# zamek.net
KiCad netlist of a schematic drawn in EAGLE
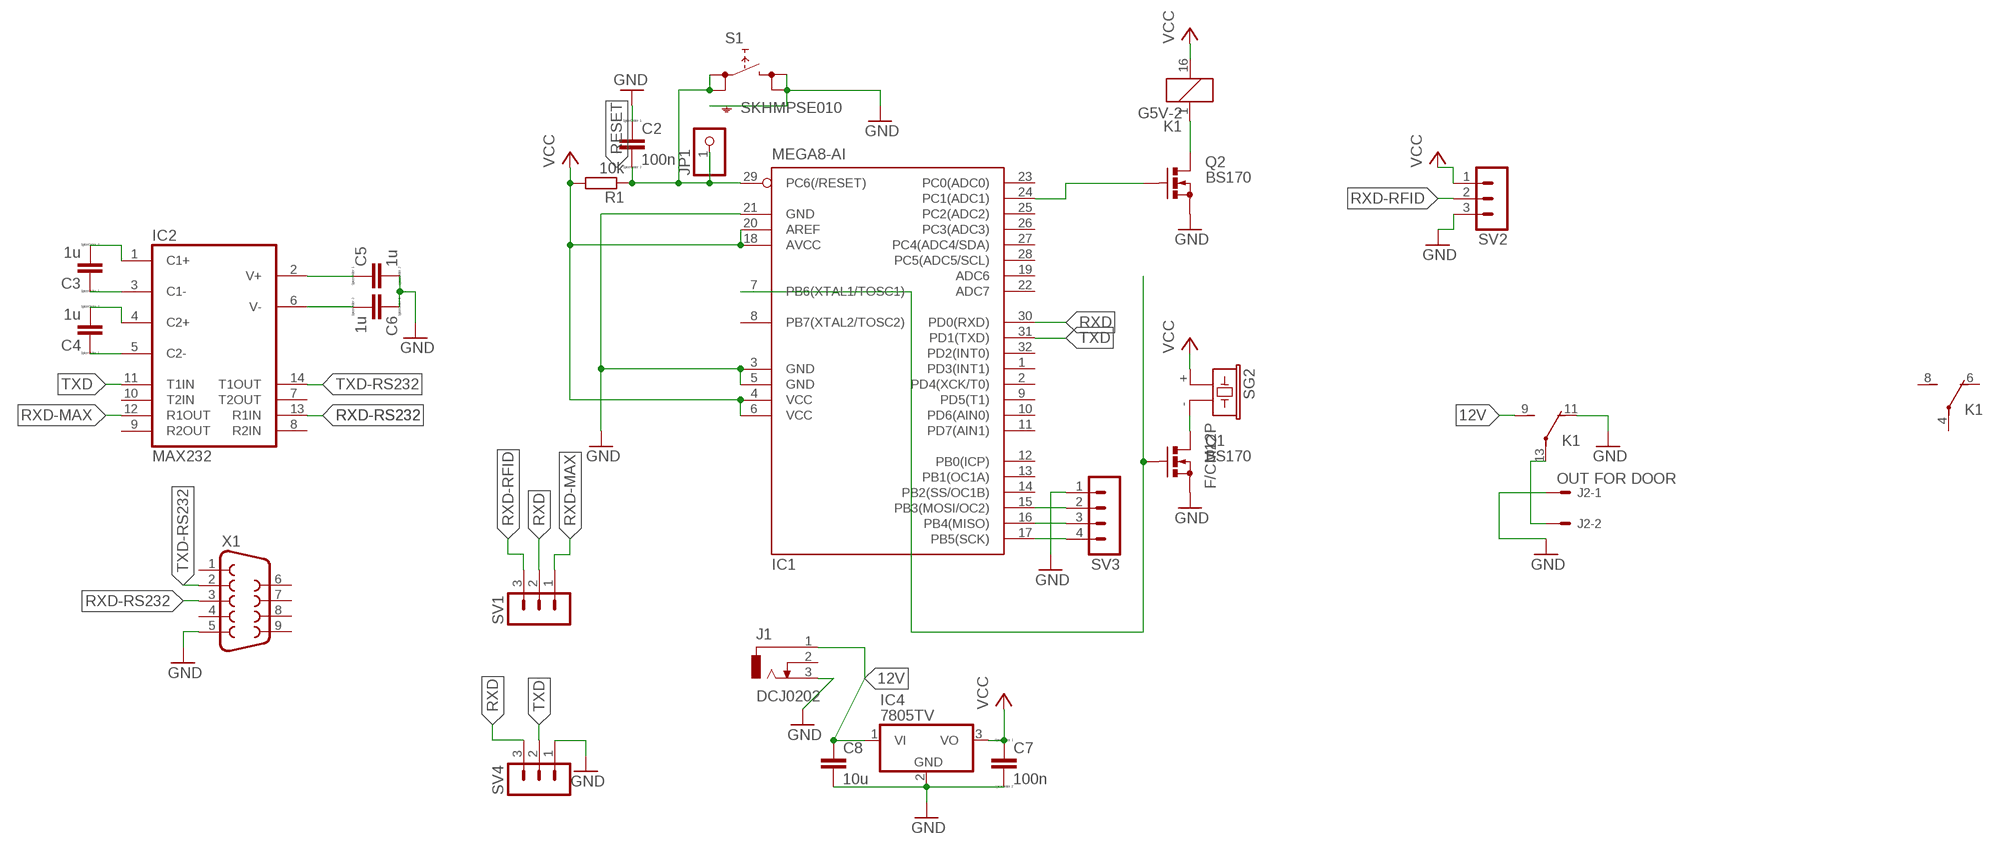
[diagram p0: schematic, sheet 1]

(export (version "E")
  (design (tool "Eeschema 10.0.6"))
  (components
    (comp (ref "C2")
      (value "100n")
      (footprint "eagle-import:C1206")
      (libsource (lib "eagle-import") (part "CC1206"))
    )
    (comp (ref "C3")
      (value "1u")
      (footprint "eagle-import:C1206")
      (libsource (lib "eagle-import") (part "CC1206"))
    )
    (comp (ref "C4")
      (value "1u")
      (footprint "eagle-import:C1206")
      (libsource (lib "eagle-import") (part "CC1206"))
    )
    (comp (ref "C5")
      (value "1u")
      (footprint "eagle-import:C1206")
      (libsource (lib "eagle-import") (part "CC1206"))
    )
    (comp (ref "C6")
      (value "1u")
      (footprint "eagle-import:C1206")
      (libsource (lib "eagle-import") (part "CC1206"))
    )
    (comp (ref "C7")
      (value "100n")
      (footprint "eagle-import:C1206")
      (libsource (lib "eagle-import") (part "CC1206"))
    )
    (comp (ref "C8")
      (value "10u")
      (footprint "eagle-import:C5B3")
      (libsource (lib "eagle-import") (part "C5/3"))
    )
    (comp (ref "IC1")
      (value "MEGA8-AI")
      (footprint "eagle-import:TQFP32-08")
      (fields (field (name "MPN") "ATMEGA8-16AU"))
      (libsource (lib "eagle-import") (part "MEGA8-AI"))
    )
    (comp (ref "IC2")
      (value "MAX232")
      (footprint "eagle-import:DIL16")
      (fields (field (name "MF") "MAXIM") (field (name "MPN") "MAX232ACPE+"))
      (libsource (lib "eagle-import") (part "MAX232"))
    )
    (comp (ref "IC4")
      (value "7805TV")
      (footprint "eagle-import:TO220V")
      (libsource (lib "eagle-import") (part "78TV05"))
    )
    (comp (ref "J1")
      (value "DCJ0202")
      (footprint "eagle-import:DCJ0202")
      (libsource (lib "eagle-import") (part "DCJ0202"))
    )
    (comp (ref "J2")
      (value "OUT FOR DOOR")
      (footprint "eagle-import:6410-02")
      (libsource (lib "eagle-import") (part "22-?-0227-2021"))
    )
    (comp (ref "JP1")
      (value "PINHD-1X1")
      (footprint "eagle-import:1X01")
      (libsource (lib "eagle-import") (part "PINHD-1X1"))
    )
    (comp (ref "K1")
      (value "G5V-2")
      (footprint "eagle-import:G5V-2")
      (fields (field (name "MPN") "G5V-2 5DC"))
      (libsource (lib "eagle-import") (part "G5V-2"))
    )
    (comp (ref "Q1")
      (value "BS170")
      (footprint "eagle-import:SOT54E")
      (libsource (lib "eagle-import") (part "BS170"))
    )
    (comp (ref "Q2")
      (value "BS170")
      (footprint "eagle-import:SOT54E")
      (libsource (lib "eagle-import") (part "BS170"))
    )
    (comp (ref "R1")
      (value "10k")
      (footprint "eagle-import:R1206")
      (libsource (lib "eagle-import") (part "R-EU_R1206"))
    )
    (comp (ref "S1")
      (value "SKHMPSE010")
      (footprint "eagle-import:SKHMPXE010")
      (libsource (lib "eagle-import") (part "SKHMPE010S"))
    )
    (comp (ref "SG2")
      (value "F/CM12P")
      (footprint "eagle-import:F_CM12P")
      (libsource (lib "eagle-import") (part "F/CM12P"))
    )
    (comp (ref "SV1")
      (value "MA03-1")
      (footprint "eagle-import:MA03-1")
      (libsource (lib "eagle-import") (part "MA03-1"))
    )
    (comp (ref "SV2")
      (value "MA03-1")
      (footprint "eagle-import:MA03-1")
      (libsource (lib "eagle-import") (part "MA03-1"))
    )
    (comp (ref "SV3")
      (value "MA04-1")
      (footprint "eagle-import:MA04-1")
      (libsource (lib "eagle-import") (part "MA04-1"))
    )
    (comp (ref "SV4")
      (value "MA03-1")
      (footprint "eagle-import:MA03-1")
      (libsource (lib "eagle-import") (part "MA03-1"))
    )
    (comp (ref "X1")
      (value "F09HP")
      (footprint "eagle-import:F09HP")
      (libsource (lib "eagle-import") (part "F09HP"))
    )
  )
  (nets
    (net (code "1") (name "12V") (class "Default")
      (node (ref "C8") (pin "1") (pinfunction "1_1") (pintype "passive"))
      (node (ref "IC4") (pin "1") (pinfunction "VI_1") (pintype "input"))
      (node (ref "J1") (pin "1") (pinfunction "1_1") (pintype "passive"))
      (node (ref "K1") (pin "9") (pinfunction "S_9") (pintype "passive"))
    )
    (net (code "2") (name "GND") (class "Default")
      (node (ref "C2") (pin "1") (pinfunction "1_1") (pintype "passive"))
      (node (ref "C5") (pin "2") (pinfunction "2_2") (pintype "passive"))
      (node (ref "C6") (pin "1") (pinfunction "1_1") (pintype "passive"))
      (node (ref "C7") (pin "2") (pinfunction "2_2") (pintype "passive"))
      (node (ref "C8") (pin "2") (pinfunction "2_2") (pintype "passive"))
      (node (ref "IC1") (pin "21") (pinfunction "GND_21") (pintype "power_in"))
      (node (ref "IC1") (pin "3") (pinfunction "GND_3") (pintype "power_in"))
      (node (ref "IC1") (pin "5") (pinfunction "GND_5") (pintype "power_in"))
      (node (ref "IC4") (pin "2") (pinfunction "GND_2") (pintype "passive"))
      (node (ref "J1") (pin "3") (pinfunction "3_3") (pintype "passive"))
      (node (ref "J2") (pin "1") (pinfunction "S_1") (pintype "passive"))
      (node (ref "K1") (pin "11") (pinfunction "O_11") (pintype "passive"))
      (node (ref "Q1") (pin "S") (pinfunction "S_S") (pintype "passive"))
      (node (ref "Q2") (pin "S") (pinfunction "S_S") (pintype "passive"))
      (node (ref "S1") (pin "3") (pinfunction "2.1_3") (pintype "passive"))
      (node (ref "S1") (pin "4") (pinfunction "2.2_4") (pintype "passive"))
      (node (ref "S1") (pin "5") (pinfunction "SH_5") (pintype "passive"))
      (node (ref "SV2") (pin "3") (pinfunction "3_3") (pintype "passive"))
      (node (ref "SV3") (pin "1") (pinfunction "1_1") (pintype "passive"))
      (node (ref "SV4") (pin "1") (pinfunction "1_1") (pintype "passive"))
      (node (ref "X1") (pin "5") (pinfunction "5_5") (pintype "passive"))
    )
    (net (code "3") (name "Net-(IC1-PB3(MOSI{slash}OC2))") (class "Default")
      (node (ref "IC1") (pin "15") (pinfunction "PB3(MOSI/OC2)_15") (pintype "bidirectional"))
      (node (ref "SV3") (pin "2") (pinfunction "2_2") (pintype "passive"))
    )
    (net (code "4") (name "Net-(IC1-PB4(MISO))") (class "Default")
      (node (ref "IC1") (pin "16") (pinfunction "PB4(MISO)_16") (pintype "bidirectional"))
      (node (ref "SV3") (pin "3") (pinfunction "3_3") (pintype "passive"))
    )
    (net (code "5") (name "Net-(IC1-PB5(SCK))") (class "Default")
      (node (ref "IC1") (pin "17") (pinfunction "PB5(SCK)_17") (pintype "bidirectional"))
      (node (ref "SV3") (pin "4") (pinfunction "4_4") (pintype "passive"))
    )
    (net (code "6") (name "Net-(IC1-PB6(XTAL1{slash}TOSC1))") (class "Default")
      (node (ref "IC1") (pin "7") (pinfunction "PB6(XTAL1/TOSC1)_7") (pintype "bidirectional"))
      (node (ref "Q1") (pin "G") (pinfunction "G_G") (pintype "passive"))
    )
    (net (code "7") (name "Net-(IC1-PC1(ADC1))") (class "Default")
      (node (ref "IC1") (pin "24") (pinfunction "PC1(ADC1)_24") (pintype "bidirectional"))
      (node (ref "Q2") (pin "G") (pinfunction "G_G") (pintype "passive"))
    )
    (net (code "8") (name "Net-(IC2A-C1+)") (class "Default")
      (node (ref "C3") (pin "2") (pinfunction "2_2") (pintype "passive"))
      (node (ref "IC2") (pin "1") (pinfunction "C1+_1") (pintype "bidirectional"))
    )
    (net (code "9") (name "Net-(IC2A-C1-)") (class "Default")
      (node (ref "C3") (pin "1") (pinfunction "1_1") (pintype "passive"))
      (node (ref "IC2") (pin "3") (pinfunction "C1-_3") (pintype "bidirectional"))
    )
    (net (code "10") (name "Net-(IC2A-C2+)") (class "Default")
      (node (ref "C4") (pin "2") (pinfunction "2_2") (pintype "passive"))
      (node (ref "IC2") (pin "4") (pinfunction "C2+_4") (pintype "bidirectional"))
    )
    (net (code "11") (name "Net-(IC2A-C2-)") (class "Default")
      (node (ref "C4") (pin "1") (pinfunction "1_1") (pintype "passive"))
      (node (ref "IC2") (pin "5") (pinfunction "C2-_5") (pintype "bidirectional"))
    )
    (net (code "12") (name "Net-(IC2A-V+)") (class "Default")
      (node (ref "C5") (pin "1") (pinfunction "1_1") (pintype "passive"))
      (node (ref "IC2") (pin "2") (pinfunction "V+_2") (pintype "bidirectional"))
    )
    (net (code "13") (name "Net-(IC2A-V-)") (class "Default")
      (node (ref "C6") (pin "2") (pinfunction "2_2") (pintype "passive"))
      (node (ref "IC2") (pin "6") (pinfunction "V-_6") (pintype "bidirectional"))
    )
    (net (code "14") (name "Net-(J2B-S)") (class "Default")
      (node (ref "J2") (pin "2") (pinfunction "S_2") (pintype "passive"))
      (node (ref "K1") (pin "13") (pinfunction "P_13") (pintype "passive"))
    )
    (net (code "15") (name "Net-(K1-Pad1)") (class "Default")
      (node (ref "K1") (pin "1") (pinfunction "1_1") (pintype "passive"))
      (node (ref "Q2") (pin "D") (pinfunction "D_D") (pintype "passive"))
    )
    (net (code "16") (name "Net-(SG2-2)") (class "Default")
      (node (ref "Q1") (pin "D") (pinfunction "D_D") (pintype "passive"))
      (node (ref "SG2") (pin "-") (pinfunction "2_-") (pintype "passive"))
    )
    (net (code "17") (name "RESET") (class "Default")
      (node (ref "C2") (pin "2") (pinfunction "2_2") (pintype "passive"))
      (node (ref "IC1") (pin "29") (pinfunction "PC6(/RESET)_29") (pintype "bidirectional"))
      (node (ref "JP1") (pin "1") (pinfunction "1_1") (pintype "passive"))
      (node (ref "R1") (pin "1") (pinfunction "1_1") (pintype "passive"))
      (node (ref "S1") (pin "1") (pinfunction "1.1_1") (pintype "passive"))
      (node (ref "S1") (pin "2") (pinfunction "1.2_2") (pintype "passive"))
    )
    (net (code "18") (name "RXD") (class "Default")
      (node (ref "IC1") (pin "30") (pinfunction "PD0(RXD)_30") (pintype "bidirectional"))
      (node (ref "SV1") (pin "2") (pinfunction "2_2") (pintype "passive"))
      (node (ref "SV4") (pin "3") (pinfunction "3_3") (pintype "passive"))
    )
    (net (code "19") (name "RXD-MAX") (class "Default")
      (node (ref "IC2") (pin "12") (pinfunction "R1OUT_12") (pintype "output"))
      (node (ref "SV1") (pin "1") (pinfunction "1_1") (pintype "passive"))
    )
    (net (code "20") (name "RXD-RFID") (class "Default")
      (node (ref "SV1") (pin "3") (pinfunction "3_3") (pintype "passive"))
      (node (ref "SV2") (pin "2") (pinfunction "2_2") (pintype "passive"))
    )
    (net (code "21") (name "RXD-RS232") (class "Default")
      (node (ref "IC2") (pin "13") (pinfunction "R1IN_13") (pintype "input"))
      (node (ref "X1") (pin "3") (pinfunction "3_3") (pintype "passive"))
    )
    (net (code "22") (name "TXD") (class "Default")
      (node (ref "IC1") (pin "31") (pinfunction "PD1(TXD)_31") (pintype "bidirectional"))
      (node (ref "IC2") (pin "11") (pinfunction "T1IN_11") (pintype "input"))
      (node (ref "SV4") (pin "2") (pinfunction "2_2") (pintype "passive"))
    )
    (net (code "23") (name "TXD-RS232") (class "Default")
      (node (ref "IC2") (pin "14") (pinfunction "T1OUT_14") (pintype "output"))
      (node (ref "X1") (pin "2") (pinfunction "2_2") (pintype "passive"))
    )
    (net (code "24") (name "VCC") (class "Default")
      (node (ref "C7") (pin "1") (pinfunction "1_1") (pintype "passive"))
      (node (ref "IC1") (pin "18") (pinfunction "AVCC_18") (pintype "power_in"))
      (node (ref "IC1") (pin "20") (pinfunction "AREF_20") (pintype "passive"))
      (node (ref "IC1") (pin "4") (pinfunction "VCC_4") (pintype "power_in"))
      (node (ref "IC1") (pin "6") (pinfunction "VCC_6") (pintype "power_in"))
      (node (ref "IC4") (pin "3") (pinfunction "VO_3") (pintype "passive"))
      (node (ref "K1") (pin "16") (pinfunction "2_16") (pintype "passive"))
      (node (ref "R1") (pin "2") (pinfunction "2_2") (pintype "passive"))
      (node (ref "SG2") (pin "+") (pinfunction "1_+") (pintype "passive"))
      (node (ref "SV2") (pin "1") (pinfunction "1_1") (pintype "passive"))
    )
    (net (code "25") (name "unconnected-(IC1-ADC6-Pad19)") (class "Default")
      (node (ref "IC1") (pin "19") (pinfunction "ADC6_19") (pintype "bidirectional"))
    )
    (net (code "26") (name "unconnected-(IC1-ADC7-Pad22)") (class "Default")
      (node (ref "IC1") (pin "22") (pinfunction "ADC7_22") (pintype "bidirectional"))
    )
    (net (code "27") (name "unconnected-(IC1-PB0(ICP)-Pad12)") (class "Default")
      (node (ref "IC1") (pin "12") (pinfunction "PB0(ICP)_12") (pintype "bidirectional"))
    )
    (net (code "28") (name "unconnected-(IC1-PB1(OC1A)-Pad13)") (class "Default")
      (node (ref "IC1") (pin "13") (pinfunction "PB1(OC1A)_13") (pintype "bidirectional"))
    )
    (net (code "29") (name "unconnected-(IC1-PB2(SS{slash}OC1B)-Pad14)") (class "Default")
      (node (ref "IC1") (pin "14") (pinfunction "PB2(SS/OC1B)_14") (pintype "bidirectional"))
    )
    (net (code "30") (name "unconnected-(IC1-PB7(XTAL2{slash}TOSC2)-Pad8)") (class "Default")
      (node (ref "IC1") (pin "8") (pinfunction "PB7(XTAL2/TOSC2)_8") (pintype "bidirectional"))
    )
    (net (code "31") (name "unconnected-(IC1-PC0(ADC0)-Pad23)") (class "Default")
      (node (ref "IC1") (pin "23") (pinfunction "PC0(ADC0)_23") (pintype "bidirectional"))
    )
    (net (code "32") (name "unconnected-(IC1-PC2(ADC2)-Pad25)") (class "Default")
      (node (ref "IC1") (pin "25") (pinfunction "PC2(ADC2)_25") (pintype "bidirectional"))
    )
    (net (code "33") (name "unconnected-(IC1-PC3(ADC3)-Pad26)") (class "Default")
      (node (ref "IC1") (pin "26") (pinfunction "PC3(ADC3)_26") (pintype "bidirectional"))
    )
    (net (code "34") (name "unconnected-(IC1-PC4(ADC4{slash}SDA)-Pad27)") (class "Default")
      (node (ref "IC1") (pin "27") (pinfunction "PC4(ADC4/SDA)_27") (pintype "bidirectional"))
    )
    (net (code "35") (name "unconnected-(IC1-PC5(ADC5{slash}SCL)-Pad28)") (class "Default")
      (node (ref "IC1") (pin "28") (pinfunction "PC5(ADC5/SCL)_28") (pintype "bidirectional"))
    )
    (net (code "36") (name "unconnected-(IC1-PD2(INT0)-Pad32)") (class "Default")
      (node (ref "IC1") (pin "32") (pinfunction "PD2(INT0)_32") (pintype "bidirectional"))
    )
    (net (code "37") (name "unconnected-(IC1-PD3(INT1)-Pad1)") (class "Default")
      (node (ref "IC1") (pin "1") (pinfunction "PD3(INT1)_1") (pintype "bidirectional"))
    )
    (net (code "38") (name "unconnected-(IC1-PD4(XCK{slash}T0)-Pad2)") (class "Default")
      (node (ref "IC1") (pin "2") (pinfunction "PD4(XCK/T0)_2") (pintype "bidirectional"))
    )
    (net (code "39") (name "unconnected-(IC1-PD5(T1)-Pad9)") (class "Default")
      (node (ref "IC1") (pin "9") (pinfunction "PD5(T1)_9") (pintype "bidirectional"))
    )
    (net (code "40") (name "unconnected-(IC1-PD6(AIN0)-Pad10)") (class "Default")
      (node (ref "IC1") (pin "10") (pinfunction "PD6(AIN0)_10") (pintype "bidirectional"))
    )
    (net (code "41") (name "unconnected-(IC1-PD7(AIN1)-Pad11)") (class "Default")
      (node (ref "IC1") (pin "11") (pinfunction "PD7(AIN1)_11") (pintype "bidirectional"))
    )
    (net (code "42") (name "unconnected-(IC2A-R2IN-Pad8)") (class "Default")
      (node (ref "IC2") (pin "8") (pinfunction "R2IN_8") (pintype "input"))
    )
    (net (code "43") (name "unconnected-(IC2A-R2OUT-Pad9)") (class "Default")
      (node (ref "IC2") (pin "9") (pinfunction "R2OUT_9") (pintype "output"))
    )
    (net (code "44") (name "unconnected-(IC2A-T2IN-Pad10)") (class "Default")
      (node (ref "IC2") (pin "10") (pinfunction "T2IN_10") (pintype "input"))
    )
    (net (code "45") (name "unconnected-(IC2A-T2OUT-Pad7)") (class "Default")
      (node (ref "IC2") (pin "7") (pinfunction "T2OUT_7") (pintype "output"))
    )
    (net (code "46") (name "unconnected-(J1-Pad2)") (class "Default")
      (node (ref "J1") (pin "2") (pinfunction "2_2") (pintype "passive"))
    )
    (net (code "47") (name "unconnected-(K1A-O-Pad6)") (class "Default")
      (node (ref "K1") (pin "6") (pinfunction "O_6") (pintype "passive"))
    )
    (net (code "48") (name "unconnected-(K1A-P-Pad4)") (class "Default")
      (node (ref "K1") (pin "4") (pinfunction "P_4") (pintype "passive"))
    )
    (net (code "49") (name "unconnected-(K1A-S-Pad8)") (class "Default")
      (node (ref "K1") (pin "8") (pinfunction "S_8") (pintype "passive"))
    )
    (net (code "50") (name "unconnected-(X1-Pad1)") (class "Default")
      (node (ref "X1") (pin "1") (pinfunction "1_1") (pintype "passive"))
    )
    (net (code "51") (name "unconnected-(X1-Pad4)") (class "Default")
      (node (ref "X1") (pin "4") (pinfunction "4_4") (pintype "passive"))
    )
    (net (code "52") (name "unconnected-(X1-Pad6)") (class "Default")
      (node (ref "X1") (pin "6") (pinfunction "6_6") (pintype "passive"))
    )
    (net (code "53") (name "unconnected-(X1-Pad7)") (class "Default")
      (node (ref "X1") (pin "7") (pinfunction "7_7") (pintype "passive"))
    )
    (net (code "54") (name "unconnected-(X1-Pad8)") (class "Default")
      (node (ref "X1") (pin "8") (pinfunction "8_8") (pintype "passive"))
    )
    (net (code "55") (name "unconnected-(X1-Pad9)") (class "Default")
      (node (ref "X1") (pin "9") (pinfunction "9_9") (pintype "passive"))
    )
  )
)
